# PushButton_SYS-LED.net
KiCad netlist of a schematic drawn in Altium Designer
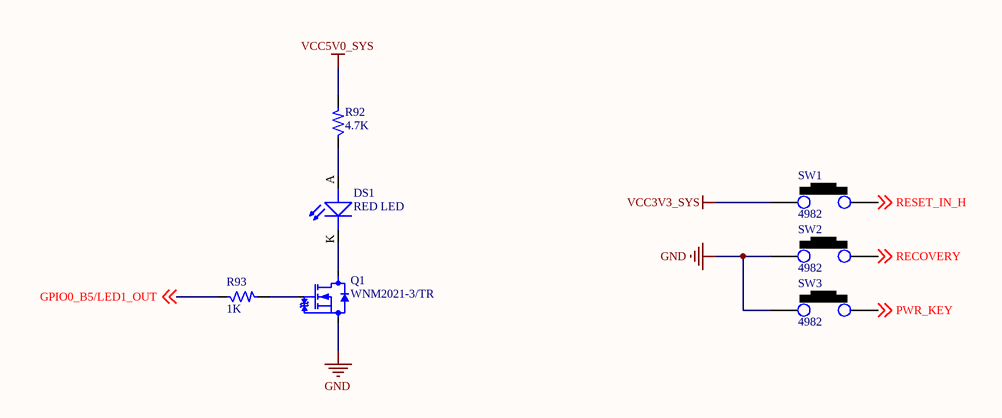
[diagram p0: PushButton_SYS-LED.SchDoc]

(export (version "E")
  (design (tool "Eeschema 10.0.6"))
  (components
    (comp (ref "DS1")
      (value "RED LED")
      (footprint "LED_0805")
      (description "Red 631nm LED Indication - Discrete 2V 0805 (2012 Metric)")
      (fields
        (field (name "MANUFACTURER") "Vishay Lite-On")
        (field (name "MANUFACTURER PART NUMBER") "LTST-C171KRKT")
      )
      (libsource (lib "EsteemPCB_SOM_Course_intlib") (part "LED_RED-2V-20mA-0805"))
    )
    (comp (ref "Q1")
      (value "WNM2021-3/TR")
      (footprint "SOT-323-3")
      (description "N Channel 20V 820mA 850mV @ 250uA 310mΩ @ 550mA,4.5V 310mW SOT-323(SC-70) MOSFET RoHS")
      (fields (field (name "MANUFACTURER") "WILLSEMI(Will Semicon)"))
      (libsource (lib "EsteemPCB_SOM_Course_intlib") (part "MOSFET-N_20V-820mA-SOT-323"))
    )
    (comp (ref "R92")
      (value "4.7K")
      (footprint "RES_0402")
      (description "4.7 kOhms ±1% 0.1W, 1/10W Chip Resistor 0402 (1005 Metric) Automotive AEC-Q200 Thick Film")
      (fields
        (field (name "MANUFACTURER") "Panasonic Electronic Components")
        (field (name "MANUFACTURER PART NUMBER") "ERJ-2RKF4701X")
      )
      (libsource (lib "EsteemPCB_SOM_Course_intlib") (part "RES_4.7K-0.1W-1%-0402"))
    )
    (comp (ref "R93")
      (value "1K")
      (footprint "RES_0402")
      (description "1 kOhms ±1% 0.1W, 1/10W Chip Resistor 0402 (1005 Metric) Anti-Sulfur Thin Film")
      (fields
        (field (name "MANUFACTURER") "Vishay Beyschlag/Draloric/BC Components")
        (field (name "MANUFACTURER PART NUMBER") "MCS04020C1001FE000")
      )
      (libsource (lib "EsteemPCB_SOM_Course_intlib") (part "RES_1K-0.1W-1%-0402"))
    )
    (comp (ref "SW1")
      (value "4982")
      (footprint "SW_177_39.3X77.7_SMD")
      (description "Tactile Switch 3x4x2mm SMD 2-Pin")
      (fields (field (name "MANUFACTURER") "NA"))
      (libsource (lib "EsteemPCB_SOM_Course_intlib") (part "SW1_4982"))
    )
    (comp (ref "SW2")
      (value "4982")
      (footprint "SW_177_39.3X77.7_SMD")
      (description "Tactile Switch 3x4x2mm SMD 2-Pin")
      (fields (field (name "MANUFACTURER") "NA"))
      (libsource (lib "EsteemPCB_SOM_Course_intlib") (part "SW1_4982"))
    )
    (comp (ref "SW3")
      (value "4982")
      (footprint "SW_177_39.3X77.7_SMD")
      (description "Tactile Switch 3x4x2mm SMD 2-Pin")
      (fields (field (name "MANUFACTURER") "NA"))
      (libsource (lib "EsteemPCB_SOM_Course_intlib") (part "SW1_4982"))
    )
  )
  (nets
    (net (code "1") (name "GND") (class "Default")
      (node (ref "Q1") (pin "2") (pinfunction "S_2") (pintype "passive"))
      (node (ref "SW2") (pin "1") (pinfunction "1_1") (pintype "passive"))
      (node (ref "SW3") (pin "1") (pinfunction "1_1") (pintype "passive"))
    )
    (net (code "2") (name "GPIO0_B5{slash}LED1_OUT") (class "Default")
      (node (ref "R93") (pin "1") (pinfunction "1_1") (pintype "passive"))
    )
    (net (code "3") (name "Net-(DS1-ANODE)") (class "Default")
      (node (ref "DS1") (pin "A") (pinfunction "ANODE_A") (pintype "passive"))
      (node (ref "R92") (pin "1") (pinfunction "1_1") (pintype "passive"))
    )
    (net (code "4") (name "Net-(DS1-CATHODE)") (class "Default")
      (node (ref "DS1") (pin "K") (pinfunction "CATHODE_K") (pintype "passive"))
      (node (ref "Q1") (pin "3") (pinfunction "D_3") (pintype "passive"))
    )
    (net (code "5") (name "Net-(Q1-G)") (class "Default")
      (node (ref "Q1") (pin "1") (pinfunction "G_1") (pintype "passive"))
      (node (ref "R93") (pin "2") (pinfunction "2_2") (pintype "passive"))
    )
    (net (code "6") (name "PWR_KEY") (class "Default")
      (node (ref "SW3") (pin "2") (pinfunction "2_2") (pintype "passive"))
    )
    (net (code "7") (name "RECOVERY") (class "Default")
      (node (ref "SW2") (pin "2") (pinfunction "2_2") (pintype "passive"))
    )
    (net (code "8") (name "RESET_IN_H") (class "Default")
      (node (ref "SW1") (pin "2") (pinfunction "2_2") (pintype "passive"))
    )
    (net (code "9") (name "VCC3V3_SYS") (class "Default")
      (node (ref "SW1") (pin "1") (pinfunction "1_1") (pintype "passive"))
    )
    (net (code "10") (name "VCC5V0_SYS") (class "Default")
      (node (ref "R92") (pin "2") (pinfunction "2_2") (pintype "passive"))
    )
  )
)
